# AK4493_Breakout_2.net
KiCad netlist of a schematic drawn in EAGLE
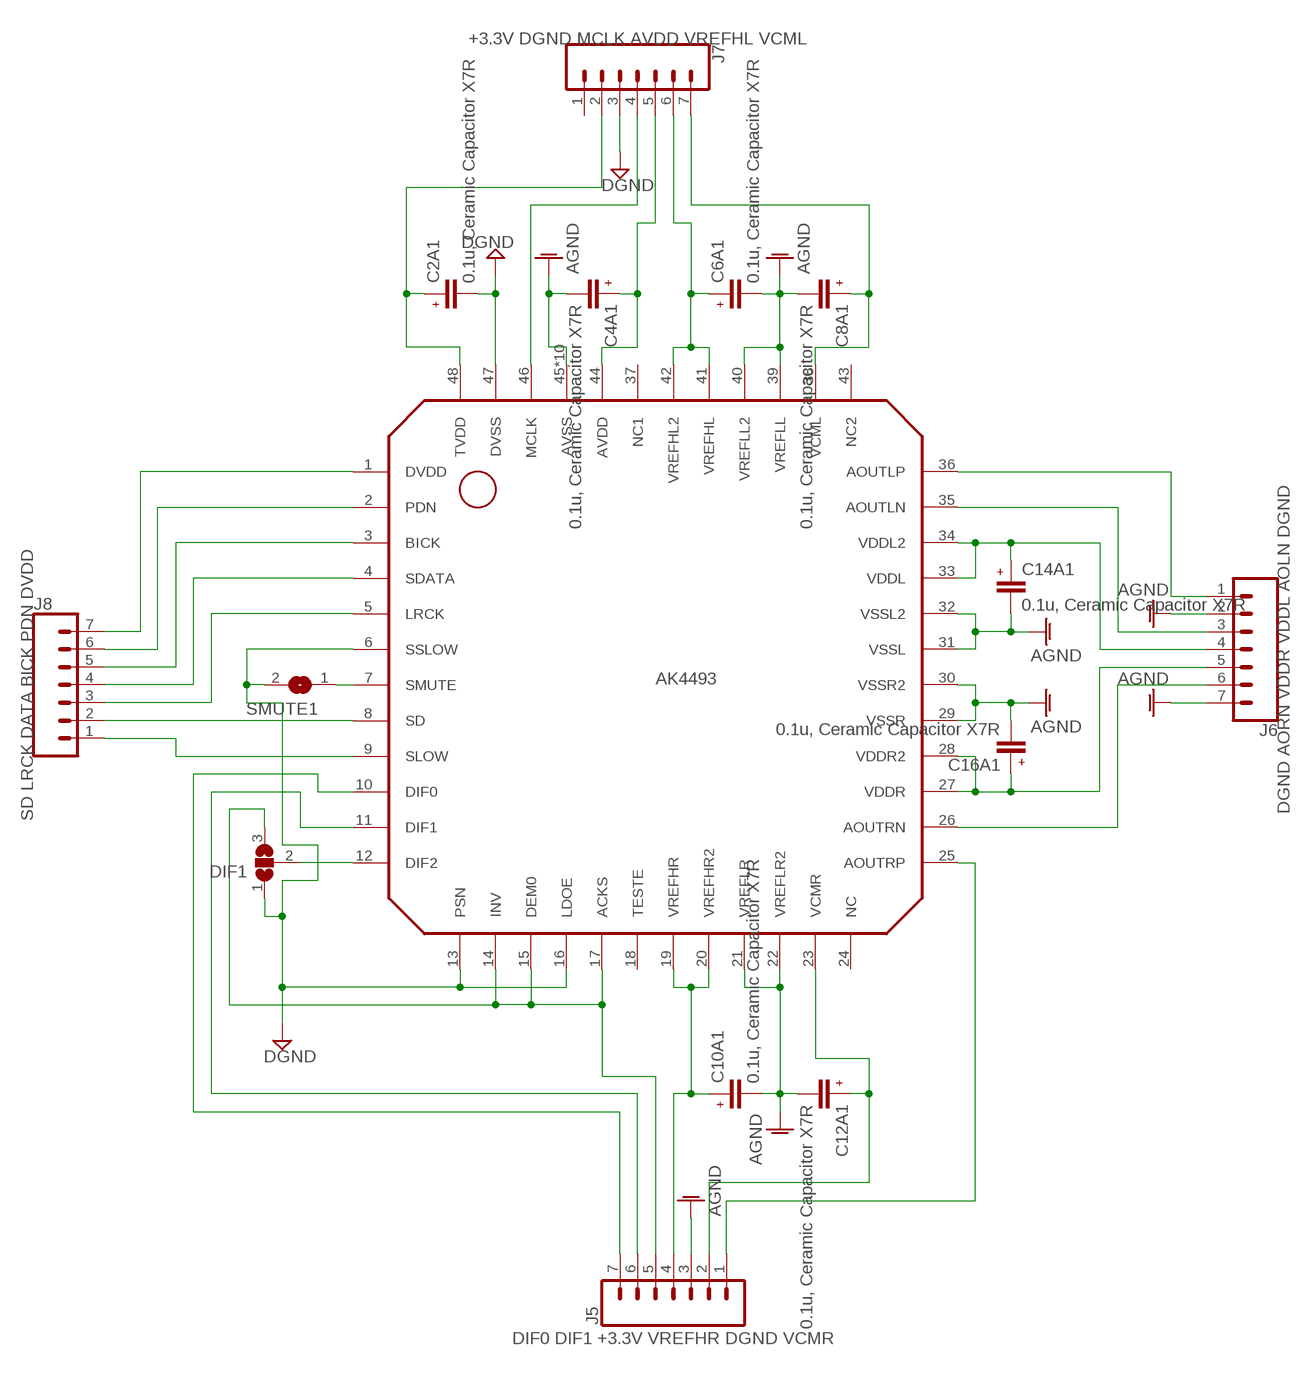
[diagram p0: schematic, sheet 1]

(export (version "E")
  (design (tool "Eeschema 10.0.6"))
  (components
    (comp (ref "C2A1")
      (value "0.1u, Ceramic Capacitor X7R")
      (footprint "eagle-import:C0603K")
      (libsource (lib "eagle-import") (part "C-POL-MLCCC0603K"))
    )
    (comp (ref "C4A1")
      (value "0.1u, Ceramic Capacitor X7R")
      (footprint "eagle-import:C0603K")
      (libsource (lib "eagle-import") (part "C-POL-MLCCC0603K"))
    )
    (comp (ref "C6A1")
      (value "0.1u, Ceramic Capacitor X7R")
      (footprint "eagle-import:C0603K")
      (libsource (lib "eagle-import") (part "C-POL-MLCCC0603K"))
    )
    (comp (ref "C8A1")
      (value "0.1u, Ceramic Capacitor X7R")
      (footprint "eagle-import:C0603K")
      (libsource (lib "eagle-import") (part "C-POL-MLCCC0603K"))
    )
    (comp (ref "C10A1")
      (value "0.1u, Ceramic Capacitor X7R")
      (footprint "eagle-import:C0603K")
      (libsource (lib "eagle-import") (part "C-POL-MLCCC0603K"))
    )
    (comp (ref "C12A1")
      (value "0.1u, Ceramic Capacitor X7R")
      (footprint "eagle-import:C0603K")
      (libsource (lib "eagle-import") (part "C-POL-MLCCC0603K"))
    )
    (comp (ref "C14A1")
      (value "0.1u, Ceramic Capacitor X7R")
      (footprint "eagle-import:C0603K")
      (libsource (lib "eagle-import") (part "C-POL-MLCCC0603K"))
    )
    (comp (ref "C16A1")
      (value "0.1u, Ceramic Capacitor X7R")
      (footprint "eagle-import:C0603K")
      (libsource (lib "eagle-import") (part "C-POL-MLCCC0603K"))
    )
    (comp (ref "DIF1")
      (value "SJ2W")
      (footprint "eagle-import:SJ_2")
      (libsource (lib "eagle-import") (part "SJ2W"))
    )
    (comp (ref "IC2")
      (value "AK4493")
      (footprint "eagle-import:LQFP48_")
      (libsource (lib "eagle-import") (part "AK4493"))
    )
    (comp (ref "J5")
      (value "CONN_07")
      (footprint "eagle-import:1X07")
      (libsource (lib "eagle-import") (part "CONN_07"))
    )
    (comp (ref "J6")
      (value "CONN_07")
      (footprint "eagle-import:1X07")
      (libsource (lib "eagle-import") (part "CONN_07"))
    )
    (comp (ref "J7")
      (value "CONN_07")
      (footprint "eagle-import:1X07")
      (libsource (lib "eagle-import") (part "CONN_07"))
    )
    (comp (ref "J8")
      (value "CONN_07")
      (footprint "eagle-import:1X07")
      (libsource (lib "eagle-import") (part "CONN_07"))
    )
    (comp (ref "SMUTE1")
      (value "SJ")
      (footprint "eagle-import:SJ")
      (libsource (lib "eagle-import") (part "SJ"))
    )
  )
  (nets
    (net (code "1") (name "AGND") (class "Default")
      (node (ref "C10A1") (pin "2") (pinfunction "2_2") (pintype "passive"))
      (node (ref "C10A1") (pin "3") (pinfunction "2_3") (pintype "passive"))
      (node (ref "C12A1") (pin "2") (pinfunction "2_2") (pintype "passive"))
      (node (ref "C12A1") (pin "3") (pinfunction "2_3") (pintype "passive"))
      (node (ref "C14A1") (pin "2") (pinfunction "2_2") (pintype "passive"))
      (node (ref "C14A1") (pin "3") (pinfunction "2_3") (pintype "passive"))
      (node (ref "C16A1") (pin "2") (pinfunction "2_2") (pintype "passive"))
      (node (ref "C16A1") (pin "3") (pinfunction "2_3") (pintype "passive"))
      (node (ref "C4A1") (pin "2") (pinfunction "2_2") (pintype "passive"))
      (node (ref "C4A1") (pin "3") (pinfunction "2_3") (pintype "passive"))
      (node (ref "C6A1") (pin "2") (pinfunction "2_2") (pintype "passive"))
      (node (ref "C6A1") (pin "3") (pinfunction "2_3") (pintype "passive"))
      (node (ref "C8A1") (pin "2") (pinfunction "2_2") (pintype "passive"))
      (node (ref "C8A1") (pin "3") (pinfunction "2_3") (pintype "passive"))
      (node (ref "IC2") (pin "21") (pinfunction "VREFLR_21") (pintype "input"))
      (node (ref "IC2") (pin "22") (pinfunction "VREFLR2_22") (pintype "input"))
      (node (ref "IC2") (pin "29") (pinfunction "VSSR_29") (pintype "power_in"))
      (node (ref "IC2") (pin "30") (pinfunction "VSSR2_30") (pintype "power_in"))
      (node (ref "IC2") (pin "31") (pinfunction "VSSL_31") (pintype "power_in"))
      (node (ref "IC2") (pin "32") (pinfunction "VSSL2_32") (pintype "power_in"))
      (node (ref "IC2") (pin "39") (pinfunction "VREFLL_39") (pintype "input"))
      (node (ref "IC2") (pin "40") (pinfunction "VREFLL2_40") (pintype "input"))
      (node (ref "IC2") (pin "45") (pinfunction "AVSS_45") (pintype "power_in"))
      (node (ref "IC2") (pin "P$1") (pinfunction "AVSS_P$1") (pintype "power_in"))
      (node (ref "IC2") (pin "P$10") (pinfunction "AVSS_P$10") (pintype "power_in"))
      (node (ref "IC2") (pin "P$17") (pinfunction "AVSS_P$17") (pintype "power_in"))
      (node (ref "IC2") (pin "P$18") (pinfunction "AVSS_P$18") (pintype "power_in"))
      (node (ref "IC2") (pin "P$2") (pinfunction "AVSS_P$2") (pintype "power_in"))
      (node (ref "IC2") (pin "P$25") (pinfunction "AVSS_P$25") (pintype "power_in"))
      (node (ref "IC2") (pin "P$4") (pinfunction "AVSS_P$4") (pintype "power_in"))
      (node (ref "IC2") (pin "P$6") (pinfunction "AVSS_P$6") (pintype "power_in"))
      (node (ref "IC2") (pin "P$8") (pinfunction "AVSS_P$8") (pintype "power_in"))
      (node (ref "J5") (pin "3") (pinfunction "3_3") (pintype "passive"))
      (node (ref "J6") (pin "2") (pinfunction "2_2") (pintype "passive"))
      (node (ref "J6") (pin "7") (pinfunction "7_7") (pintype "passive"))
    )
    (net (code "2") (name "DGND") (class "Default")
      (node (ref "C2A1") (pin "2") (pinfunction "2_2") (pintype "passive"))
      (node (ref "C2A1") (pin "3") (pinfunction "2_3") (pintype "passive"))
      (node (ref "DIF1") (pin "1") (pinfunction "1_1") (pintype "passive"))
      (node (ref "IC2") (pin "13") (pinfunction "PSN_13") (pintype "input"))
      (node (ref "IC2") (pin "16") (pinfunction "LDOE_16") (pintype "input"))
      (node (ref "IC2") (pin "47") (pinfunction "DVSS_47") (pintype "power_in"))
      (node (ref "IC2") (pin "6") (pinfunction "SSLOW_6") (pintype "input"))
      (node (ref "J7") (pin "3") (pinfunction "3_3") (pintype "passive"))
      (node (ref "SMUTE1") (pin "2") (pinfunction "2_2") (pintype "passive"))
    )
    (net (code "3") (name "Net-(IC2-ACKS)") (class "Default")
      (node (ref "DIF1") (pin "3") (pinfunction "3_3") (pintype "passive"))
      (node (ref "IC2") (pin "14") (pinfunction "INV_14") (pintype "input"))
      (node (ref "IC2") (pin "15") (pinfunction "DEM0_15") (pintype "input"))
      (node (ref "IC2") (pin "17") (pinfunction "ACKS_17") (pintype "input"))
      (node (ref "J5") (pin "5") (pinfunction "5_5") (pintype "passive"))
    )
    (net (code "4") (name "Net-(IC2-AOUTLN)") (class "Default")
      (node (ref "IC2") (pin "35") (pinfunction "AOUTLN_35") (pintype "output"))
      (node (ref "J6") (pin "3") (pinfunction "3_3") (pintype "passive"))
    )
    (net (code "5") (name "Net-(IC2-AOUTLP)") (class "Default")
      (node (ref "IC2") (pin "36") (pinfunction "AOUTLP_36") (pintype "output"))
      (node (ref "J6") (pin "1") (pinfunction "1_1") (pintype "passive"))
    )
    (net (code "6") (name "Net-(IC2-AOUTRN)") (class "Default")
      (node (ref "IC2") (pin "26") (pinfunction "AOUTRN_26") (pintype "output"))
      (node (ref "J6") (pin "6") (pinfunction "6_6") (pintype "passive"))
    )
    (net (code "7") (name "Net-(IC2-AOUTRP)") (class "Default")
      (node (ref "IC2") (pin "25") (pinfunction "AOUTRP_25") (pintype "output"))
      (node (ref "J5") (pin "1") (pinfunction "1_1") (pintype "passive"))
    )
    (net (code "8") (name "Net-(IC2-AVDD)") (class "Default")
      (node (ref "C4A1") (pin "1") (pinfunction "1_1") (pintype "passive"))
      (node (ref "IC2") (pin "44") (pinfunction "AVDD_44") (pintype "power_in"))
      (node (ref "J7") (pin "5") (pinfunction "5_5") (pintype "passive"))
    )
    (net (code "9") (name "Net-(IC2-BICK)") (class "Default")
      (node (ref "IC2") (pin "3") (pinfunction "BICK_3") (pintype "input"))
      (node (ref "J8") (pin "5") (pinfunction "5_5") (pintype "passive"))
    )
    (net (code "10") (name "Net-(IC2-DIF0)") (class "Default")
      (node (ref "IC2") (pin "10") (pinfunction "DIF0_10") (pintype "input"))
      (node (ref "J5") (pin "7") (pinfunction "7_7") (pintype "passive"))
    )
    (net (code "11") (name "Net-(IC2-DIF1)") (class "Default")
      (node (ref "IC2") (pin "11") (pinfunction "DIF1_11") (pintype "input"))
      (node (ref "J5") (pin "6") (pinfunction "6_6") (pintype "passive"))
    )
    (net (code "12") (name "Net-(IC2-DIF2)") (class "Default")
      (node (ref "DIF1") (pin "2") (pinfunction "2_2") (pintype "passive"))
      (node (ref "IC2") (pin "12") (pinfunction "DIF2_12") (pintype "input"))
    )
    (net (code "13") (name "Net-(IC2-DVDD)") (class "Default")
      (node (ref "IC2") (pin "1") (pinfunction "DVDD_1") (pintype "power_in"))
      (node (ref "J8") (pin "7") (pinfunction "7_7") (pintype "passive"))
    )
    (net (code "14") (name "Net-(IC2-LRCK)") (class "Default")
      (node (ref "IC2") (pin "5") (pinfunction "LRCK_5") (pintype "input"))
      (node (ref "J8") (pin "3") (pinfunction "3_3") (pintype "passive"))
    )
    (net (code "15") (name "Net-(IC2-MCLK)") (class "Default")
      (node (ref "IC2") (pin "46") (pinfunction "MCLK_46") (pintype "input"))
      (node (ref "J7") (pin "4") (pinfunction "4_4") (pintype "passive"))
    )
    (net (code "16") (name "Net-(IC2-PDN)") (class "Default")
      (node (ref "IC2") (pin "2") (pinfunction "PDN_2") (pintype "input"))
      (node (ref "J8") (pin "6") (pinfunction "6_6") (pintype "passive"))
    )
    (net (code "17") (name "Net-(IC2-SD)") (class "Default")
      (node (ref "IC2") (pin "8") (pinfunction "SD_8") (pintype "input"))
      (node (ref "J8") (pin "2") (pinfunction "2_2") (pintype "passive"))
    )
    (net (code "18") (name "Net-(IC2-SDATA)") (class "Default")
      (node (ref "IC2") (pin "4") (pinfunction "SDATA_4") (pintype "input"))
      (node (ref "J8") (pin "4") (pinfunction "4_4") (pintype "passive"))
    )
    (net (code "19") (name "Net-(IC2-SLOW)") (class "Default")
      (node (ref "IC2") (pin "9") (pinfunction "SLOW_9") (pintype "input"))
      (node (ref "J8") (pin "1") (pinfunction "1_1") (pintype "passive"))
    )
    (net (code "20") (name "Net-(IC2-SMUTE)") (class "Default")
      (node (ref "IC2") (pin "7") (pinfunction "SMUTE_7") (pintype "input"))
      (node (ref "SMUTE1") (pin "1") (pinfunction "1_1") (pintype "passive"))
    )
    (net (code "21") (name "Net-(IC2-TVDD)") (class "Default")
      (node (ref "C2A1") (pin "1") (pinfunction "1_1") (pintype "passive"))
      (node (ref "IC2") (pin "48") (pinfunction "TVDD_48") (pintype "power_in"))
      (node (ref "J7") (pin "2") (pinfunction "2_2") (pintype "passive"))
    )
    (net (code "22") (name "Net-(IC2-VCML)") (class "Default")
      (node (ref "C8A1") (pin "1") (pinfunction "1_1") (pintype "passive"))
      (node (ref "IC2") (pin "38") (pinfunction "VCML_38") (pintype "power_in"))
      (node (ref "J7") (pin "7") (pinfunction "7_7") (pintype "passive"))
    )
    (net (code "23") (name "Net-(IC2-VCMR)") (class "Default")
      (node (ref "C12A1") (pin "1") (pinfunction "1_1") (pintype "passive"))
      (node (ref "IC2") (pin "23") (pinfunction "VCMR_23") (pintype "power_in"))
      (node (ref "J5") (pin "2") (pinfunction "2_2") (pintype "passive"))
    )
    (net (code "24") (name "Net-(IC2-VDDL)") (class "Default")
      (node (ref "C14A1") (pin "1") (pinfunction "1_1") (pintype "passive"))
      (node (ref "IC2") (pin "33") (pinfunction "VDDL_33") (pintype "power_in"))
      (node (ref "IC2") (pin "34") (pinfunction "VDDL2_34") (pintype "power_in"))
      (node (ref "J6") (pin "4") (pinfunction "4_4") (pintype "passive"))
    )
    (net (code "25") (name "Net-(IC2-VDDR)") (class "Default")
      (node (ref "C16A1") (pin "1") (pinfunction "1_1") (pintype "passive"))
      (node (ref "IC2") (pin "27") (pinfunction "VDDR_27") (pintype "power_in"))
      (node (ref "IC2") (pin "28") (pinfunction "VDDR2_28") (pintype "power_in"))
      (node (ref "J6") (pin "5") (pinfunction "5_5") (pintype "passive"))
    )
    (net (code "26") (name "Net-(IC2-VREFHL)") (class "Default")
      (node (ref "C6A1") (pin "1") (pinfunction "1_1") (pintype "passive"))
      (node (ref "IC2") (pin "41") (pinfunction "VREFHL_41") (pintype "input"))
      (node (ref "IC2") (pin "42") (pinfunction "VREFHL2_42") (pintype "input"))
      (node (ref "J7") (pin "6") (pinfunction "6_6") (pintype "passive"))
    )
    (net (code "27") (name "Net-(IC2-VREFHR)") (class "Default")
      (node (ref "C10A1") (pin "1") (pinfunction "1_1") (pintype "passive"))
      (node (ref "IC2") (pin "19") (pinfunction "VREFHR_19") (pintype "input"))
      (node (ref "IC2") (pin "20") (pinfunction "VREFHR2_20") (pintype "input"))
      (node (ref "J5") (pin "4") (pinfunction "4_4") (pintype "passive"))
    )
    (net (code "28") (name "unconnected-(IC2-NC-Pad24)") (class "Default")
      (node (ref "IC2") (pin "24") (pinfunction "NC_24") (pintype "no_connect"))
    )
    (net (code "29") (name "unconnected-(IC2-NC1-Pad37)") (class "Default")
      (node (ref "IC2") (pin "37") (pinfunction "NC1_37") (pintype "no_connect"))
    )
    (net (code "30") (name "unconnected-(IC2-NC2-Pad43)") (class "Default")
      (node (ref "IC2") (pin "43") (pinfunction "NC2_43") (pintype "no_connect"))
    )
    (net (code "31") (name "unconnected-(IC2-TESTE-Pad18)") (class "Default")
      (node (ref "IC2") (pin "18") (pinfunction "TESTE_18") (pintype "input"))
    )
    (net (code "32") (name "unconnected-(J7-Pad1)") (class "Default")
      (node (ref "J7") (pin "1") (pinfunction "1_1") (pintype "passive"))
    )
  )
)
